# MyCard_Ver9.net
KiCad netlist of a schematic drawn in EAGLE
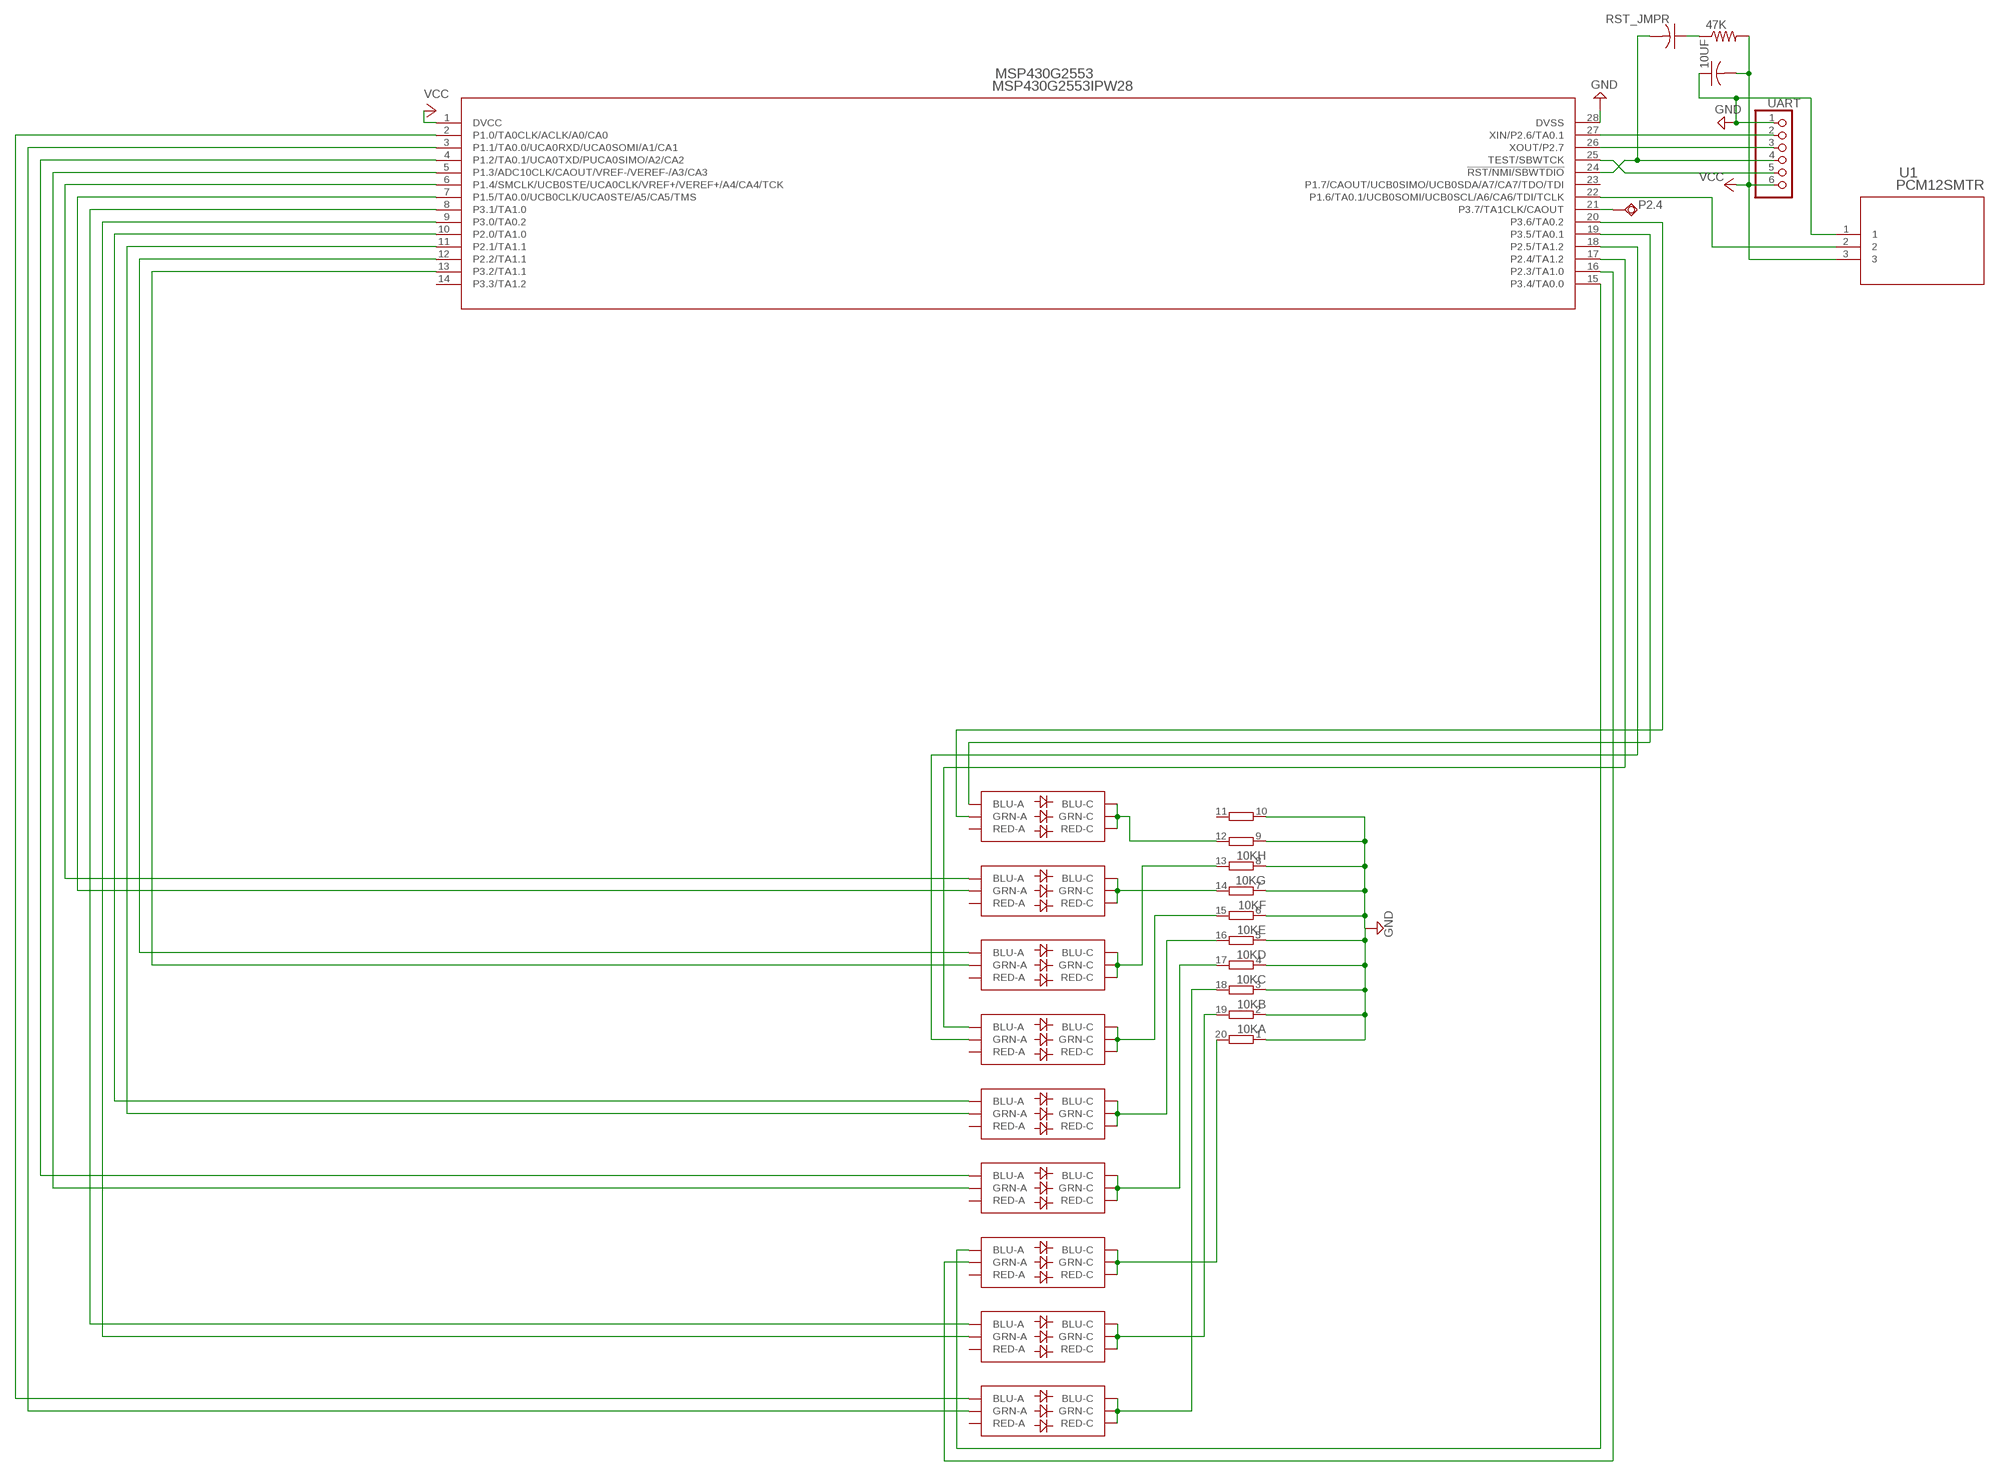
[diagram p0: schematic, sheet 1, part 1 of 2]
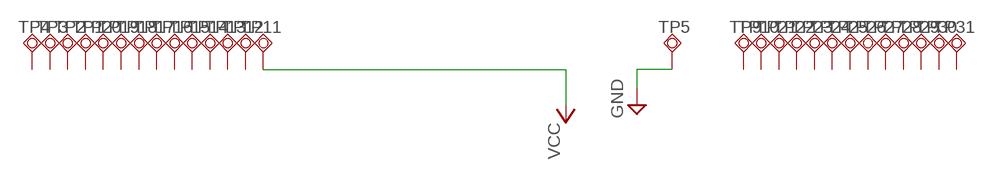
[diagram p1: schematic, sheet 1, part 2 of 2]

(export (version "E")
  (design (tool "Eeschema 10.0.6"))
  (components
    (comp (ref "0")
      (value "RGB")
      (footprint "eagle-import:PLCC-6-LED")
      (libsource (lib "eagle-import") (part "LED-RGBPLCC-6"))
    )
    (comp (ref "1")
      (value "RGB")
      (footprint "eagle-import:PLCC-6-LED")
      (libsource (lib "eagle-import") (part "LED-RGBPLCC-6"))
    )
    (comp (ref "2")
      (value "RGB")
      (footprint "eagle-import:PLCC-6-LED")
      (libsource (lib "eagle-import") (part "LED-RGBPLCC-6"))
    )
    (comp (ref "3")
      (value "RGB")
      (footprint "eagle-import:PLCC-6-LED")
      (libsource (lib "eagle-import") (part "LED-RGBPLCC-6"))
    )
    (comp (ref "4")
      (value "RGB")
      (footprint "eagle-import:PLCC-6-LED")
      (libsource (lib "eagle-import") (part "LED-RGBPLCC-6"))
    )
    (comp (ref "5")
      (value "RGB")
      (footprint "eagle-import:PLCC-6-LED")
      (libsource (lib "eagle-import") (part "LED-RGBPLCC-6"))
    )
    (comp (ref "6")
      (value "RGB")
      (footprint "eagle-import:PLCC-6-LED")
      (libsource (lib "eagle-import") (part "LED-RGBPLCC-6"))
    )
    (comp (ref "7")
      (value "RGB")
      (footprint "eagle-import:PLCC-6-LED")
      (libsource (lib "eagle-import") (part "LED-RGBPLCC-6"))
    )
    (comp (ref "8")
      (value "RGB")
      (footprint "eagle-import:PLCC-6-LED")
      (libsource (lib "eagle-import") (part "LED-RGBPLCC-6"))
    )
    (comp (ref "10K")
      (value "10R-NSOMC")
      (footprint "eagle-import:SOMC20")
      (libsource (lib "eagle-import") (part "10R-NSOMC"))
    )
    (comp (ref "10UF")
      (value "C-USC0805")
      (footprint "eagle-import:C0805")
      (libsource (lib "eagle-import") (part "C-USC0805"))
    )
    (comp (ref "47K")
      (value "R-US_R0805")
      (footprint "eagle-import:R0805")
      (libsource (lib "eagle-import") (part "R-US_R0805"))
    )
    (comp (ref "MSP430G2553")
      (value "MSP430G2553IPW28")
      (footprint "eagle-import:PW28")
      (fields (field (name "COPYRIGHT") "Copyright (C) 2023 Ultra Librarian. All rights reserved."))
      (libsource (lib "eagle-import") (part "MSP430G2553IPW28"))
    )
    (comp (ref "P2.4")
      (value "TPSQTP20R")
      (footprint "eagle-import:TP20R")
      (libsource (lib "eagle-import") (part "TPSQTP20R"))
    )
    (comp (ref "RST_JMPR")
      (value "C-USC0805")
      (footprint "eagle-import:C0805")
      (libsource (lib "eagle-import") (part "C-USC0805"))
    )
    (comp (ref "TP1")
      (value "TPSQTP20SQ")
      (footprint "eagle-import:TP20SQ")
      (libsource (lib "eagle-import") (part "TPSQTP20SQ"))
    )
    (comp (ref "TP2")
      (value "TPSQTP20SQ")
      (footprint "eagle-import:TP20SQ")
      (libsource (lib "eagle-import") (part "TPSQTP20SQ"))
    )
    (comp (ref "TP3")
      (value "TPSQTP20SQ")
      (footprint "eagle-import:TP20SQ")
      (libsource (lib "eagle-import") (part "TPSQTP20SQ"))
    )
    (comp (ref "TP4")
      (value "TPSQTP20SQ")
      (footprint "eagle-import:TP20SQ")
      (libsource (lib "eagle-import") (part "TPSQTP20SQ"))
    )
    (comp (ref "TP5")
      (value "TPSQTP20SQ")
      (footprint "eagle-import:TP20SQ")
      (libsource (lib "eagle-import") (part "TPSQTP20SQ"))
    )
    (comp (ref "TP9")
      (value "TPSQTP20SQ")
      (footprint "eagle-import:TP20SQ")
      (libsource (lib "eagle-import") (part "TPSQTP20SQ"))
    )
    (comp (ref "TP10")
      (value "TPSQTP20SQ")
      (footprint "eagle-import:TP20SQ")
      (libsource (lib "eagle-import") (part "TPSQTP20SQ"))
    )
    (comp (ref "TP11")
      (value "TPSQTP20SQ")
      (footprint "eagle-import:TP20SQ")
      (libsource (lib "eagle-import") (part "TPSQTP20SQ"))
    )
    (comp (ref "TP12")
      (value "TPSQTP20SQ")
      (footprint "eagle-import:TP20SQ")
      (libsource (lib "eagle-import") (part "TPSQTP20SQ"))
    )
    (comp (ref "TP13")
      (value "TPSQTP20SQ")
      (footprint "eagle-import:TP20SQ")
      (libsource (lib "eagle-import") (part "TPSQTP20SQ"))
    )
    (comp (ref "TP14")
      (value "TPSQTP20SQ")
      (footprint "eagle-import:TP20SQ")
      (libsource (lib "eagle-import") (part "TPSQTP20SQ"))
    )
    (comp (ref "TP15")
      (value "TPSQTP20SQ")
      (footprint "eagle-import:TP20SQ")
      (libsource (lib "eagle-import") (part "TPSQTP20SQ"))
    )
    (comp (ref "TP16")
      (value "TPSQTP20SQ")
      (footprint "eagle-import:TP20SQ")
      (libsource (lib "eagle-import") (part "TPSQTP20SQ"))
    )
    (comp (ref "TP17")
      (value "TPSQTP20SQ")
      (footprint "eagle-import:TP20SQ")
      (libsource (lib "eagle-import") (part "TPSQTP20SQ"))
    )
    (comp (ref "TP18")
      (value "TPSQTP20SQ")
      (footprint "eagle-import:TP20SQ")
      (libsource (lib "eagle-import") (part "TPSQTP20SQ"))
    )
    (comp (ref "TP19")
      (value "TPSQTP20SQ")
      (footprint "eagle-import:TP20SQ")
      (libsource (lib "eagle-import") (part "TPSQTP20SQ"))
    )
    (comp (ref "TP20")
      (value "TPSQTP20SQ")
      (footprint "eagle-import:TP20SQ")
      (libsource (lib "eagle-import") (part "TPSQTP20SQ"))
    )
    (comp (ref "TP21")
      (value "TPSQTP20SQ")
      (footprint "eagle-import:TP20SQ")
      (libsource (lib "eagle-import") (part "TPSQTP20SQ"))
    )
    (comp (ref "TP22")
      (value "TPSQTP20SQ")
      (footprint "eagle-import:TP20SQ")
      (libsource (lib "eagle-import") (part "TPSQTP20SQ"))
    )
    (comp (ref "TP23")
      (value "TPSQTP20SQ")
      (footprint "eagle-import:TP20SQ")
      (libsource (lib "eagle-import") (part "TPSQTP20SQ"))
    )
    (comp (ref "TP24")
      (value "TPSQTP20SQ")
      (footprint "eagle-import:TP20SQ")
      (libsource (lib "eagle-import") (part "TPSQTP20SQ"))
    )
    (comp (ref "TP25")
      (value "TPSQTP20SQ")
      (footprint "eagle-import:TP20SQ")
      (libsource (lib "eagle-import") (part "TPSQTP20SQ"))
    )
    (comp (ref "TP26")
      (value "TPSQTP20SQ")
      (footprint "eagle-import:TP20SQ")
      (libsource (lib "eagle-import") (part "TPSQTP20SQ"))
    )
    (comp (ref "TP27")
      (value "TPSQTP20SQ")
      (footprint "eagle-import:TP20SQ")
      (libsource (lib "eagle-import") (part "TPSQTP20SQ"))
    )
    (comp (ref "TP28")
      (value "TPSQTP20SQ")
      (footprint "eagle-import:TP20SQ")
      (libsource (lib "eagle-import") (part "TPSQTP20SQ"))
    )
    (comp (ref "TP29")
      (value "TPSQTP20SQ")
      (footprint "eagle-import:TP20SQ")
      (libsource (lib "eagle-import") (part "TPSQTP20SQ"))
    )
    (comp (ref "TP30")
      (value "TPSQTP20SQ")
      (footprint "eagle-import:TP20SQ")
      (libsource (lib "eagle-import") (part "TPSQTP20SQ"))
    )
    (comp (ref "TP31")
      (value "TPSQTP20SQ")
      (footprint "eagle-import:TP20SQ")
      (libsource (lib "eagle-import") (part "TPSQTP20SQ"))
    )
    (comp (ref "U1")
      (value "PCM12SMTR")
      (footprint "eagle-import:PCM12SMTR_CNK")
      (fields (field (name "COPYRIGHT") "Copyright (C) 2023 Ultra Librarian. All rights reserved."))
      (libsource (lib "eagle-import") (part "PCM12SMTR"))
    )
    (comp (ref "UART")
      (value "PINHD-1X6B")
      (footprint "eagle-import:1X06-BIG")
      (libsource (lib "eagle-import") (part "PINHD-1X6B"))
    )
  )
  (nets
    (net (code "1") (name "GND") (class "Default")
      (node (ref "10K") (pin "1") (pinfunction "1_1") (pintype "passive"))
      (node (ref "10K") (pin "10") (pinfunction "1_10") (pintype "passive"))
      (node (ref "10K") (pin "2") (pinfunction "1_2") (pintype "passive"))
      (node (ref "10K") (pin "3") (pinfunction "1_3") (pintype "passive"))
      (node (ref "10K") (pin "4") (pinfunction "1_4") (pintype "passive"))
      (node (ref "10K") (pin "5") (pinfunction "1_5") (pintype "passive"))
      (node (ref "10K") (pin "6") (pinfunction "1_6") (pintype "passive"))
      (node (ref "10K") (pin "7") (pinfunction "1_7") (pintype "passive"))
      (node (ref "10K") (pin "8") (pinfunction "1_8") (pintype "passive"))
      (node (ref "10K") (pin "9") (pinfunction "1_9") (pintype "passive"))
      (node (ref "10UF") (pin "1") (pinfunction "1_1") (pintype "passive"))
      (node (ref "MSP430G2553") (pin "28") (pinfunction "DVSS_28") (pintype "power_in"))
      (node (ref "TP5") (pin "TP") (pinfunction "TP_TP") (pintype "input"))
      (node (ref "U1") (pin "1") (pinfunction "1_1") (pintype "passive"))
      (node (ref "UART") (pin "1") (pinfunction "1_1") (pintype "passive"))
    )
    (net (code "2") (name "Net-(0-BLU-A)") (class "Default")
      (node (ref "0") (pin "AB") (pinfunction "BLU-A_AB") (pintype "bidirectional"))
      (node (ref "MSP430G2553") (pin "2") (pinfunction "P1.0/TA0CLK/ACLK/A0/CA0_2") (pintype "bidirectional"))
    )
    (net (code "3") (name "Net-(0-BLU-C)") (class "Default")
      (node (ref "0") (pin "CB") (pinfunction "BLU-C_CB") (pintype "bidirectional"))
      (node (ref "0") (pin "CG") (pinfunction "GRN-C_CG") (pintype "bidirectional"))
      (node (ref "0") (pin "CR") (pinfunction "RED-C_CR") (pintype "bidirectional"))
      (node (ref "10K") (pin "18") (pinfunction "2_18") (pintype "passive"))
    )
    (net (code "4") (name "Net-(0-GRN-A)") (class "Default")
      (node (ref "0") (pin "AG") (pinfunction "GRN-A_AG") (pintype "bidirectional"))
      (node (ref "MSP430G2553") (pin "3") (pinfunction "P1.1/TA0.0/UCA0RXD/UCA0SOMI/A1/CA1_3") (pintype "bidirectional"))
    )
    (net (code "5") (name "Net-(1-BLU-A)") (class "Default")
      (node (ref "1") (pin "AB") (pinfunction "BLU-A_AB") (pintype "bidirectional"))
      (node (ref "MSP430G2553") (pin "8") (pinfunction "P3.1/TA1.0_8") (pintype "bidirectional"))
    )
    (net (code "6") (name "Net-(1-BLU-C)") (class "Default")
      (node (ref "1") (pin "CB") (pinfunction "BLU-C_CB") (pintype "bidirectional"))
      (node (ref "1") (pin "CG") (pinfunction "GRN-C_CG") (pintype "bidirectional"))
      (node (ref "1") (pin "CR") (pinfunction "RED-C_CR") (pintype "bidirectional"))
      (node (ref "10K") (pin "19") (pinfunction "2_19") (pintype "passive"))
    )
    (net (code "7") (name "Net-(1-GRN-A)") (class "Default")
      (node (ref "1") (pin "AG") (pinfunction "GRN-A_AG") (pintype "bidirectional"))
      (node (ref "MSP430G2553") (pin "9") (pinfunction "P3.0/TA0.2_9") (pintype "bidirectional"))
    )
    (net (code "8") (name "Net-(2-BLU-A)") (class "Default")
      (node (ref "2") (pin "AB") (pinfunction "BLU-A_AB") (pintype "bidirectional"))
      (node (ref "MSP430G2553") (pin "15") (pinfunction "P3.4/TA0.0_15") (pintype "bidirectional"))
    )
    (net (code "9") (name "Net-(2-GRN-A)") (class "Default")
      (node (ref "2") (pin "AG") (pinfunction "GRN-A_AG") (pintype "bidirectional"))
      (node (ref "MSP430G2553") (pin "16") (pinfunction "P2.3/TA1.0_16") (pintype "bidirectional"))
    )
    (net (code "10") (name "Net-(3-BLU-A)") (class "Default")
      (node (ref "3") (pin "AB") (pinfunction "BLU-A_AB") (pintype "bidirectional"))
      (node (ref "MSP430G2553") (pin "4") (pinfunction "P1.2/TA0.1/UCA0TXD/PUCA0SIMO/A2/CA2_4") (pintype "bidirectional"))
    )
    (net (code "11") (name "Net-(3-GRN-A)") (class "Default")
      (node (ref "3") (pin "AG") (pinfunction "GRN-A_AG") (pintype "bidirectional"))
      (node (ref "MSP430G2553") (pin "5") (pinfunction "P1.3/ADC10CLK/CAOUT/VREF-/VEREF-/A3/CA3_5") (pintype "bidirectional"))
    )
    (net (code "12") (name "Net-(4-BLU-A)") (class "Default")
      (node (ref "4") (pin "AB") (pinfunction "BLU-A_AB") (pintype "bidirectional"))
      (node (ref "MSP430G2553") (pin "10") (pinfunction "P2.0/TA1.0_10") (pintype "bidirectional"))
    )
    (net (code "13") (name "Net-(4-GRN-A)") (class "Default")
      (node (ref "4") (pin "AG") (pinfunction "GRN-A_AG") (pintype "bidirectional"))
      (node (ref "MSP430G2553") (pin "11") (pinfunction "P2.1/TA1.1_11") (pintype "bidirectional"))
    )
    (net (code "14") (name "Net-(5-BLU-A)") (class "Default")
      (node (ref "5") (pin "AB") (pinfunction "BLU-A_AB") (pintype "bidirectional"))
      (node (ref "MSP430G2553") (pin "17") (pinfunction "P2.4/TA1.2_17") (pintype "bidirectional"))
    )
    (net (code "15") (name "Net-(5-GRN-A)") (class "Default")
      (node (ref "5") (pin "AG") (pinfunction "GRN-A_AG") (pintype "bidirectional"))
      (node (ref "MSP430G2553") (pin "18") (pinfunction "P2.5/TA1.2_18") (pintype "bidirectional"))
    )
    (net (code "16") (name "Net-(6-BLU-A)") (class "Default")
      (node (ref "6") (pin "AB") (pinfunction "BLU-A_AB") (pintype "bidirectional"))
      (node (ref "MSP430G2553") (pin "6") (pinfunction "P1.4/SMCLK/UCB0STE/UCA0CLK/VREF+/VEREF+/A4/CA4/TCK_6") (pintype "bidirectional"))
    )
    (net (code "17") (name "Net-(6-GRN-A)") (class "Default")
      (node (ref "6") (pin "AG") (pinfunction "GRN-A_AG") (pintype "bidirectional"))
      (node (ref "MSP430G2553") (pin "7") (pinfunction "P1.5/TA0.0/UCB0CLK/UCA0STE/A5/CA5/TMS_7") (pintype "bidirectional"))
    )
    (net (code "18") (name "Net-(7-BLU-A)") (class "Default")
      (node (ref "7") (pin "AB") (pinfunction "BLU-A_AB") (pintype "bidirectional"))
      (node (ref "MSP430G2553") (pin "12") (pinfunction "P2.2/TA1.1_12") (pintype "bidirectional"))
    )
    (net (code "19") (name "Net-(7-GRN-A)") (class "Default")
      (node (ref "7") (pin "AG") (pinfunction "GRN-A_AG") (pintype "bidirectional"))
      (node (ref "MSP430G2553") (pin "13") (pinfunction "P3.2/TA1.1_13") (pintype "bidirectional"))
    )
    (net (code "20") (name "Net-(8-BLU-A)") (class "Default")
      (node (ref "8") (pin "AB") (pinfunction "BLU-A_AB") (pintype "bidirectional"))
      (node (ref "MSP430G2553") (pin "19") (pinfunction "P3.5/TA0.1_19") (pintype "bidirectional"))
    )
    (net (code "21") (name "Net-(8-GRN-A)") (class "Default")
      (node (ref "8") (pin "AG") (pinfunction "GRN-A_AG") (pintype "bidirectional"))
      (node (ref "MSP430G2553") (pin "20") (pinfunction "P3.6/TA0.2_20") (pintype "bidirectional"))
    )
    (net (code "22") (name "Net-(10KA-2)") (class "Default")
      (node (ref "10K") (pin "20") (pinfunction "2_20") (pintype "passive"))
      (node (ref "2") (pin "CB") (pinfunction "BLU-C_CB") (pintype "bidirectional"))
      (node (ref "2") (pin "CG") (pinfunction "GRN-C_CG") (pintype "bidirectional"))
      (node (ref "2") (pin "CR") (pinfunction "RED-C_CR") (pintype "bidirectional"))
    )
    (net (code "23") (name "Net-(10KD-2)") (class "Default")
      (node (ref "10K") (pin "17") (pinfunction "2_17") (pintype "passive"))
      (node (ref "3") (pin "CB") (pinfunction "BLU-C_CB") (pintype "bidirectional"))
      (node (ref "3") (pin "CG") (pinfunction "GRN-C_CG") (pintype "bidirectional"))
      (node (ref "3") (pin "CR") (pinfunction "RED-C_CR") (pintype "bidirectional"))
    )
    (net (code "24") (name "Net-(10KE-2)") (class "Default")
      (node (ref "10K") (pin "16") (pinfunction "2_16") (pintype "passive"))
      (node (ref "4") (pin "CB") (pinfunction "BLU-C_CB") (pintype "bidirectional"))
      (node (ref "4") (pin "CG") (pinfunction "GRN-C_CG") (pintype "bidirectional"))
      (node (ref "4") (pin "CR") (pinfunction "RED-C_CR") (pintype "bidirectional"))
    )
    (net (code "25") (name "Net-(10KF-2)") (class "Default")
      (node (ref "10K") (pin "15") (pinfunction "2_15") (pintype "passive"))
      (node (ref "5") (pin "CB") (pinfunction "BLU-C_CB") (pintype "bidirectional"))
      (node (ref "5") (pin "CG") (pinfunction "GRN-C_CG") (pintype "bidirectional"))
      (node (ref "5") (pin "CR") (pinfunction "RED-C_CR") (pintype "bidirectional"))
    )
    (net (code "26") (name "Net-(10KG-2)") (class "Default")
      (node (ref "10K") (pin "14") (pinfunction "2_14") (pintype "passive"))
      (node (ref "6") (pin "CB") (pinfunction "BLU-C_CB") (pintype "bidirectional"))
      (node (ref "6") (pin "CG") (pinfunction "GRN-C_CG") (pintype "bidirectional"))
      (node (ref "6") (pin "CR") (pinfunction "RED-C_CR") (pintype "bidirectional"))
    )
    (net (code "27") (name "Net-(10KH-2)") (class "Default")
      (node (ref "10K") (pin "13") (pinfunction "2_13") (pintype "passive"))
      (node (ref "7") (pin "CB") (pinfunction "BLU-C_CB") (pintype "bidirectional"))
      (node (ref "7") (pin "CG") (pinfunction "GRN-C_CG") (pintype "bidirectional"))
      (node (ref "7") (pin "CR") (pinfunction "RED-C_CR") (pintype "bidirectional"))
    )
    (net (code "28") (name "Net-(10KI-2)") (class "Default")
      (node (ref "10K") (pin "12") (pinfunction "2_12") (pintype "passive"))
      (node (ref "8") (pin "CB") (pinfunction "BLU-C_CB") (pintype "bidirectional"))
      (node (ref "8") (pin "CG") (pinfunction "GRN-C_CG") (pintype "bidirectional"))
      (node (ref "8") (pin "CR") (pinfunction "RED-C_CR") (pintype "bidirectional"))
    )
    (net (code "29") (name "Net-(47K-Pad1)") (class "Default")
      (node (ref "47K") (pin "1") (pinfunction "1_1") (pintype "passive"))
      (node (ref "RST_JMPR") (pin "1") (pinfunction "1_1") (pintype "passive"))
    )
    (net (code "30") (name "Net-(MSP430G2553-P1.6{slash}TA0.1{slash}UCB0SOMI{slash}UCB0SCL{slash}A6{slash}CA6{slash}TDI{slash}TCLK)") (class "Default")
      (node (ref "MSP430G2553") (pin "22") (pinfunction "P1.6/TA0.1/UCB0SOMI/UCB0SCL/A6/CA6/TDI/TCLK_22") (pintype "bidirectional"))
      (node (ref "U1") (pin "2") (pinfunction "2_2") (pintype "passive"))
    )
    (net (code "31") (name "Net-(MSP430G2553-P3.7{slash}TA1CLK{slash}CAOUT)") (class "Default")
      (node (ref "MSP430G2553") (pin "21") (pinfunction "P3.7/TA1CLK/CAOUT_21") (pintype "bidirectional"))
      (node (ref "P2.4") (pin "TP") (pinfunction "TP_TP") (pintype "input"))
    )
    (net (code "32") (name "Net-(MSP430G2553-TEST{slash}SBWTCK)") (class "Default")
      (node (ref "MSP430G2553") (pin "25") (pinfunction "TEST/SBWTCK_25") (pintype "bidirectional"))
      (node (ref "UART") (pin "5") (pinfunction "5_5") (pintype "passive"))
    )
    (net (code "33") (name "Net-(MSP430G2553-XIN{slash}P2.6{slash}TA0.1)") (class "Default")
      (node (ref "MSP430G2553") (pin "27") (pinfunction "XIN/P2.6/TA0.1_27") (pintype "bidirectional"))
      (node (ref "UART") (pin "2") (pinfunction "2_2") (pintype "passive"))
    )
    (net (code "34") (name "Net-(MSP430G2553-XOUT{slash}P2.7)") (class "Default")
      (node (ref "MSP430G2553") (pin "26") (pinfunction "XOUT/P2.7_26") (pintype "bidirectional"))
      (node (ref "UART") (pin "3") (pinfunction "3_3") (pintype "passive"))
    )
    (net (code "35") (name "Net-(MSP430G2553-~{RST{slash}NMI{slash}SBWTDIO})") (class "Default")
      (node (ref "MSP430G2553") (pin "24") (pinfunction "~{RST/NMI/SBWTDIO}_24") (pintype "bidirectional"))
      (node (ref "RST_JMPR") (pin "2") (pinfunction "2_2") (pintype "passive"))
      (node (ref "UART") (pin "4") (pinfunction "4_4") (pintype "passive"))
    )
    (net (code "36") (name "VCC") (class "Default")
      (node (ref "10UF") (pin "2") (pinfunction "2_2") (pintype "passive"))
      (node (ref "47K") (pin "2") (pinfunction "2_2") (pintype "passive"))
      (node (ref "MSP430G2553") (pin "1") (pinfunction "DVCC_1") (pintype "power_in"))
      (node (ref "TP11") (pin "TP") (pinfunction "TP_TP") (pintype "input"))
      (node (ref "U1") (pin "3") (pinfunction "3_3") (pintype "passive"))
      (node (ref "UART") (pin "6") (pinfunction "6_6") (pintype "passive"))
    )
    (net (code "37") (name "unconnected-(0-RED-A-PadAR)") (class "Default")
      (node (ref "0") (pin "AR") (pinfunction "RED-A_AR") (pintype "bidirectional"))
    )
    (net (code "38") (name "unconnected-(1-RED-A-PadAR)") (class "Default")
      (node (ref "1") (pin "AR") (pinfunction "RED-A_AR") (pintype "bidirectional"))
    )
    (net (code "39") (name "unconnected-(2-RED-A-PadAR)") (class "Default")
      (node (ref "2") (pin "AR") (pinfunction "RED-A_AR") (pintype "bidirectional"))
    )
    (net (code "40") (name "unconnected-(3-RED-A-PadAR)") (class "Default")
      (node (ref "3") (pin "AR") (pinfunction "RED-A_AR") (pintype "bidirectional"))
    )
    (net (code "41") (name "unconnected-(4-RED-A-PadAR)") (class "Default")
      (node (ref "4") (pin "AR") (pinfunction "RED-A_AR") (pintype "bidirectional"))
    )
    (net (code "42") (name "unconnected-(5-RED-A-PadAR)") (class "Default")
      (node (ref "5") (pin "AR") (pinfunction "RED-A_AR") (pintype "bidirectional"))
    )
    (net (code "43") (name "unconnected-(6-RED-A-PadAR)") (class "Default")
      (node (ref "6") (pin "AR") (pinfunction "RED-A_AR") (pintype "bidirectional"))
    )
    (net (code "44") (name "unconnected-(7-RED-A-PadAR)") (class "Default")
      (node (ref "7") (pin "AR") (pinfunction "RED-A_AR") (pintype "bidirectional"))
    )
    (net (code "45") (name "unconnected-(8-RED-A-PadAR)") (class "Default")
      (node (ref "8") (pin "AR") (pinfunction "RED-A_AR") (pintype "bidirectional"))
    )
    (net (code "46") (name "unconnected-(10KJ-2-Pad11)") (class "Default")
      (node (ref "10K") (pin "11") (pinfunction "2_11") (pintype "passive"))
    )
    (net (code "47") (name "unconnected-(MSP430G2553-P1.7{slash}CAOUT{slash}UCB0SIMO{slash}UCB0SDA{slash}A7{slash}CA7{slash}TDO{slash}TDI-Pad23)") (class "Default")
      (node (ref "MSP430G2553") (pin "23") (pinfunction "P1.7/CAOUT/UCB0SIMO/UCB0SDA/A7/CA7/TDO/TDI_23") (pintype "bidirectional"))
    )
    (net (code "48") (name "unconnected-(MSP430G2553-P3.3{slash}TA1.2-Pad14)") (class "Default")
      (node (ref "MSP430G2553") (pin "14") (pinfunction "P3.3/TA1.2_14") (pintype "bidirectional"))
    )
    (net (code "49") (name "unconnected-(TP1-PadTP)") (class "Default")
      (node (ref "TP1") (pin "TP") (pinfunction "TP_TP") (pintype "input"))
    )
    (net (code "50") (name "unconnected-(TP2-PadTP)") (class "Default")
      (node (ref "TP2") (pin "TP") (pinfunction "TP_TP") (pintype "input"))
    )
    (net (code "51") (name "unconnected-(TP3-PadTP)") (class "Default")
      (node (ref "TP3") (pin "TP") (pinfunction "TP_TP") (pintype "input"))
    )
    (net (code "52") (name "unconnected-(TP4-PadTP)") (class "Default")
      (node (ref "TP4") (pin "TP") (pinfunction "TP_TP") (pintype "input"))
    )
    (net (code "53") (name "unconnected-(TP9-PadTP)") (class "Default")
      (node (ref "TP9") (pin "TP") (pinfunction "TP_TP") (pintype "input"))
    )
    (net (code "54") (name "unconnected-(TP10-PadTP)") (class "Default")
      (node (ref "TP10") (pin "TP") (pinfunction "TP_TP") (pintype "input"))
    )
    (net (code "55") (name "unconnected-(TP12-PadTP)") (class "Default")
      (node (ref "TP12") (pin "TP") (pinfunction "TP_TP") (pintype "input"))
    )
    (net (code "56") (name "unconnected-(TP13-PadTP)") (class "Default")
      (node (ref "TP13") (pin "TP") (pinfunction "TP_TP") (pintype "input"))
    )
    (net (code "57") (name "unconnected-(TP14-PadTP)") (class "Default")
      (node (ref "TP14") (pin "TP") (pinfunction "TP_TP") (pintype "input"))
    )
    (net (code "58") (name "unconnected-(TP15-PadTP)") (class "Default")
      (node (ref "TP15") (pin "TP") (pinfunction "TP_TP") (pintype "input"))
    )
    (net (code "59") (name "unconnected-(TP16-PadTP)") (class "Default")
      (node (ref "TP16") (pin "TP") (pinfunction "TP_TP") (pintype "input"))
    )
    (net (code "60") (name "unconnected-(TP17-PadTP)") (class "Default")
      (node (ref "TP17") (pin "TP") (pinfunction "TP_TP") (pintype "input"))
    )
    (net (code "61") (name "unconnected-(TP18-PadTP)") (class "Default")
      (node (ref "TP18") (pin "TP") (pinfunction "TP_TP") (pintype "input"))
    )
    (net (code "62") (name "unconnected-(TP19-PadTP)") (class "Default")
      (node (ref "TP19") (pin "TP") (pinfunction "TP_TP") (pintype "input"))
    )
    (net (code "63") (name "unconnected-(TP20-PadTP)") (class "Default")
      (node (ref "TP20") (pin "TP") (pinfunction "TP_TP") (pintype "input"))
    )
    (net (code "64") (name "unconnected-(TP21-PadTP)") (class "Default")
      (node (ref "TP21") (pin "TP") (pinfunction "TP_TP") (pintype "input"))
    )
    (net (code "65") (name "unconnected-(TP22-PadTP)") (class "Default")
      (node (ref "TP22") (pin "TP") (pinfunction "TP_TP") (pintype "input"))
    )
    (net (code "66") (name "unconnected-(TP23-PadTP)") (class "Default")
      (node (ref "TP23") (pin "TP") (pinfunction "TP_TP") (pintype "input"))
    )
    (net (code "67") (name "unconnected-(TP24-PadTP)") (class "Default")
      (node (ref "TP24") (pin "TP") (pinfunction "TP_TP") (pintype "input"))
    )
    (net (code "68") (name "unconnected-(TP25-PadTP)") (class "Default")
      (node (ref "TP25") (pin "TP") (pinfunction "TP_TP") (pintype "input"))
    )
    (net (code "69") (name "unconnected-(TP26-PadTP)") (class "Default")
      (node (ref "TP26") (pin "TP") (pinfunction "TP_TP") (pintype "input"))
    )
    (net (code "70") (name "unconnected-(TP27-PadTP)") (class "Default")
      (node (ref "TP27") (pin "TP") (pinfunction "TP_TP") (pintype "input"))
    )
    (net (code "71") (name "unconnected-(TP28-PadTP)") (class "Default")
      (node (ref "TP28") (pin "TP") (pinfunction "TP_TP") (pintype "input"))
    )
    (net (code "72") (name "unconnected-(TP29-PadTP)") (class "Default")
      (node (ref "TP29") (pin "TP") (pinfunction "TP_TP") (pintype "input"))
    )
    (net (code "73") (name "unconnected-(TP30-PadTP)") (class "Default")
      (node (ref "TP30") (pin "TP") (pinfunction "TP_TP") (pintype "input"))
    )
    (net (code "74") (name "unconnected-(TP31-PadTP)") (class "Default")
      (node (ref "TP31") (pin "TP") (pinfunction "TP_TP") (pintype "input"))
    )
  )
)
